# Driver_High_Current.net
KiCad netlist of a schematic drawn in Altium Designer
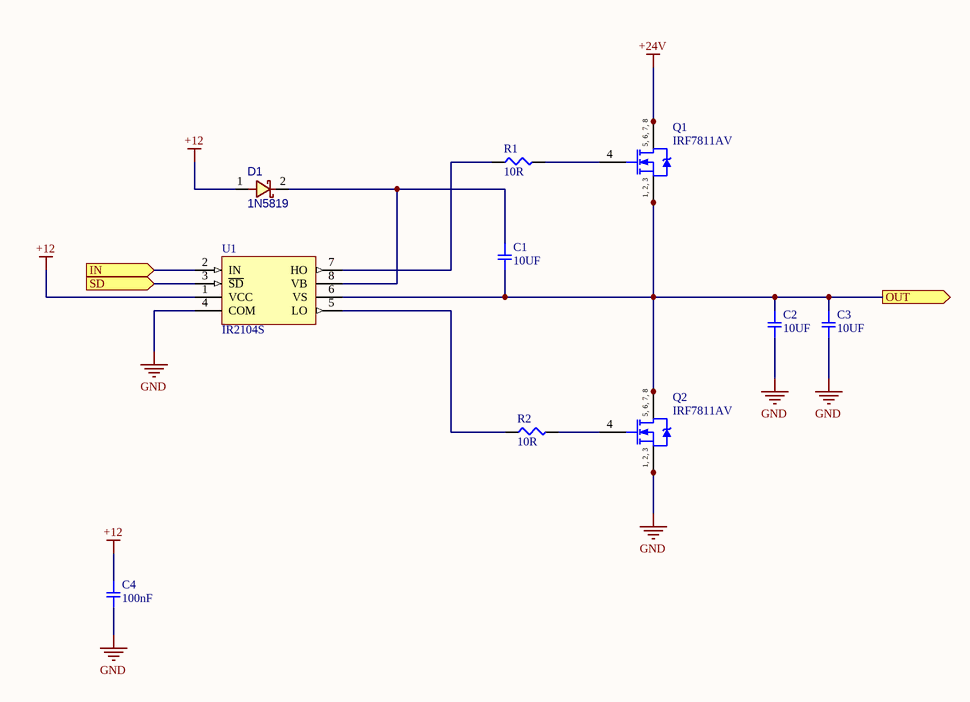
[diagram p0: Driver High Current.SchDoc]

(export (version "E")
  (design (tool "Eeschema 10.0.6"))
  (components
    (comp (ref "C1")
      (value "10UF")
      (footprint "SMD-1206C")
      (description "CAP CER 10UF 250V X7T 1206")
      (fields
        (field (name "DIGI-KEY PART NUMBER") "490-13989-1-ND")
        (field (name "PART NUMBER") "GC331AD72E333KX01D")
      )
      (libsource (lib "capacitor_murata_1206") (part "GC331AD72E333KX01D"))
    )
    (comp (ref "C2")
      (value "10UF")
      (footprint "SMD-1206C")
      (description "CAP CER 10UF 250V X7T 1206")
      (fields
        (field (name "DIGI-KEY PART NUMBER") "490-13989-1-ND")
        (field (name "PART NUMBER") "GC331AD72E333KX01D")
      )
      (libsource (lib "capacitor_murata_1206") (part "GC331AD72E333KX01D"))
    )
    (comp (ref "C3")
      (value "10UF")
      (footprint "SMD-1206C")
      (description "CAP CER 10UF 250V X7T 1206")
      (fields
        (field (name "DIGI-KEY PART NUMBER") "490-13989-1-ND")
        (field (name "PART NUMBER") "GC331AD72E333KX01D")
      )
      (libsource (lib "capacitor_murata_1206") (part "GC331AD72E333KX01D"))
    )
    (comp (ref "C4")
      (value "100nF")
      (footprint "SMD-0805C")
      (description "CAP CER 100nF 50V X7T 0805")
      (fields
        (field (name "DIGI-KEY PART NUMBER") "490-13986-1-ND")
        (field (name "PART NUMBER") "GC321AD72E103KX01D")
      )
      (libsource (lib "capacitor_murata_0805") (part "GC321AD72E103KX01D"))
    )
    (comp (ref "D1")
      (value "1N5819")
      (footprint "D_SOD123W")
      (description "DIODE, SCHOTTKY, 40V, 1A")
      (fields (field (name "MANF") "DIODES") (field (name "MANF_P#") "1N5819HW-7-F"))
      (libsource (lib "chila ") (part "DIODE_SMD_SCHOTTKY_1N5819"))
    )
    (comp (ref "Q1")
      (value "IRF7811AV")
      (footprint "SOIC-8")
      (description "HEXFET Power MOSFET")
      (fields (field (name "PUBLISHER") "Altium Limited"))
      (libsource (lib "IR Discrete MOSFET - Power") (part "IRF7811AV"))
    )
    (comp (ref "Q2")
      (value "IRF7811AV")
      (footprint "SOIC-8")
      (description "HEXFET Power MOSFET")
      (fields (field (name "PUBLISHER") "Altium Limited"))
      (libsource (lib "IR Discrete MOSFET - Power") (part "IRF7811AV"))
    )
    (comp (ref "R1")
      (value "10R")
      (footprint "SMD-0805-RES")
      (description "RES SMD 10R OHM 1% 1/3W 0805")
      (fields (field (name "PART NUMBER") "ERJ-6BQF1R0V") (field (name "DIGI-KEY PART NUMBER") "P17499CT-ND"))
      (libsource (lib "Panasonic_ERJ_0805") (part "ERJ-6BQF1R0V"))
    )
    (comp (ref "R2")
      (value "10R")
      (footprint "SMD-0805-RES")
      (description "RES SMD 10R OHM 1% 1/3W 0805")
      (fields (field (name "PART NUMBER") "ERJ-6BQF1R0V") (field (name "DIGI-KEY PART NUMBER") "P17499CT-ND"))
      (libsource (lib "Panasonic_ERJ_0805") (part "ERJ-6BQF1R0V"))
    )
    (comp (ref "U1")
      (value "IR2104S")
      (footprint "SOIC-8")
      (description "High and Low Side Driver")
      (fields (field (name "PUBLISHER") "Altium Limited"))
      (libsource (lib "IR Interface Bridge Driver") (part "IR2104S"))
    )
  )
  (nets
    (net (code "1") (name "+12") (class "Default")
      (node (ref "C4") (pin "1") (pinfunction "1_1") (pintype "passive"))
      (node (ref "D1") (pin "1") (pinfunction "1_1") (pintype "passive"))
      (node (ref "U1") (pin "1") (pinfunction "VCC_1") (pintype "power_in"))
    )
    (net (code "2") (name "+24V") (class "Default")
      (node (ref "Q1") (pin "5") (pinfunction "D_5") (pintype "passive"))
      (node (ref "Q1") (pin "6") (pinfunction "D_6") (pintype "passive"))
      (node (ref "Q1") (pin "7") (pinfunction "D_7") (pintype "passive"))
      (node (ref "Q1") (pin "8") (pinfunction "D_8") (pintype "passive"))
    )
    (net (code "3") (name "/IN") (class "Default")
      (node (ref "U1") (pin "2") (pinfunction "IN_2") (pintype "input"))
    )
    (net (code "4") (name "/OUT") (class "Default")
      (node (ref "C1") (pin "2") (pinfunction "2_2") (pintype "passive"))
      (node (ref "C2") (pin "1") (pinfunction "1_1") (pintype "passive"))
      (node (ref "C3") (pin "1") (pinfunction "1_1") (pintype "passive"))
      (node (ref "Q1") (pin "1") (pinfunction "S_1") (pintype "passive"))
      (node (ref "Q1") (pin "2") (pinfunction "S_2") (pintype "passive"))
      (node (ref "Q1") (pin "3") (pinfunction "S_3") (pintype "passive"))
      (node (ref "Q2") (pin "5") (pinfunction "D_5") (pintype "passive"))
      (node (ref "Q2") (pin "6") (pinfunction "D_6") (pintype "passive"))
      (node (ref "Q2") (pin "7") (pinfunction "D_7") (pintype "passive"))
      (node (ref "Q2") (pin "8") (pinfunction "D_8") (pintype "passive"))
      (node (ref "U1") (pin "6") (pinfunction "VS_6") (pintype "power_in"))
    )
    (net (code "5") (name "/SD") (class "Default")
      (node (ref "U1") (pin "3") (pinfunction "~{SD}_3") (pintype "input"))
    )
    (net (code "6") (name "GND") (class "Default")
      (node (ref "C2") (pin "2") (pinfunction "2_2") (pintype "passive"))
      (node (ref "C3") (pin "2") (pinfunction "2_2") (pintype "passive"))
      (node (ref "C4") (pin "2") (pinfunction "2_2") (pintype "passive"))
      (node (ref "Q2") (pin "1") (pinfunction "S_1") (pintype "passive"))
      (node (ref "Q2") (pin "2") (pinfunction "S_2") (pintype "passive"))
      (node (ref "Q2") (pin "3") (pinfunction "S_3") (pintype "passive"))
      (node (ref "U1") (pin "4") (pinfunction "COM_4") (pintype "power_in"))
    )
    (net (code "7") (name "Net-(Q1-G)") (class "Default")
      (node (ref "Q1") (pin "4") (pinfunction "G_4") (pintype "passive"))
      (node (ref "R1") (pin "2") (pinfunction "2_2") (pintype "passive"))
    )
    (net (code "8") (name "Net-(Q2-G)") (class "Default")
      (node (ref "Q2") (pin "4") (pinfunction "G_4") (pintype "passive"))
      (node (ref "R2") (pin "2") (pinfunction "2_2") (pintype "passive"))
    )
    (net (code "9") (name "Net-(U1-HO)") (class "Default")
      (node (ref "R1") (pin "1") (pinfunction "1_1") (pintype "passive"))
      (node (ref "U1") (pin "7") (pinfunction "HO_7") (pintype "output"))
    )
    (net (code "10") (name "Net-(U1-LO)") (class "Default")
      (node (ref "R2") (pin "1") (pinfunction "1_1") (pintype "passive"))
      (node (ref "U1") (pin "5") (pinfunction "LO_5") (pintype "output"))
    )
    (net (code "11") (name "Net-(U1-VB)") (class "Default")
      (node (ref "C1") (pin "1") (pinfunction "1_1") (pintype "passive"))
      (node (ref "D1") (pin "2") (pinfunction "2_2") (pintype "passive"))
      (node (ref "U1") (pin "8") (pinfunction "VB_8") (pintype "power_in"))
    )
  )
)
